# Servo2015_Logic_V1_2.net
KiCad netlist of a schematic drawn in EAGLE
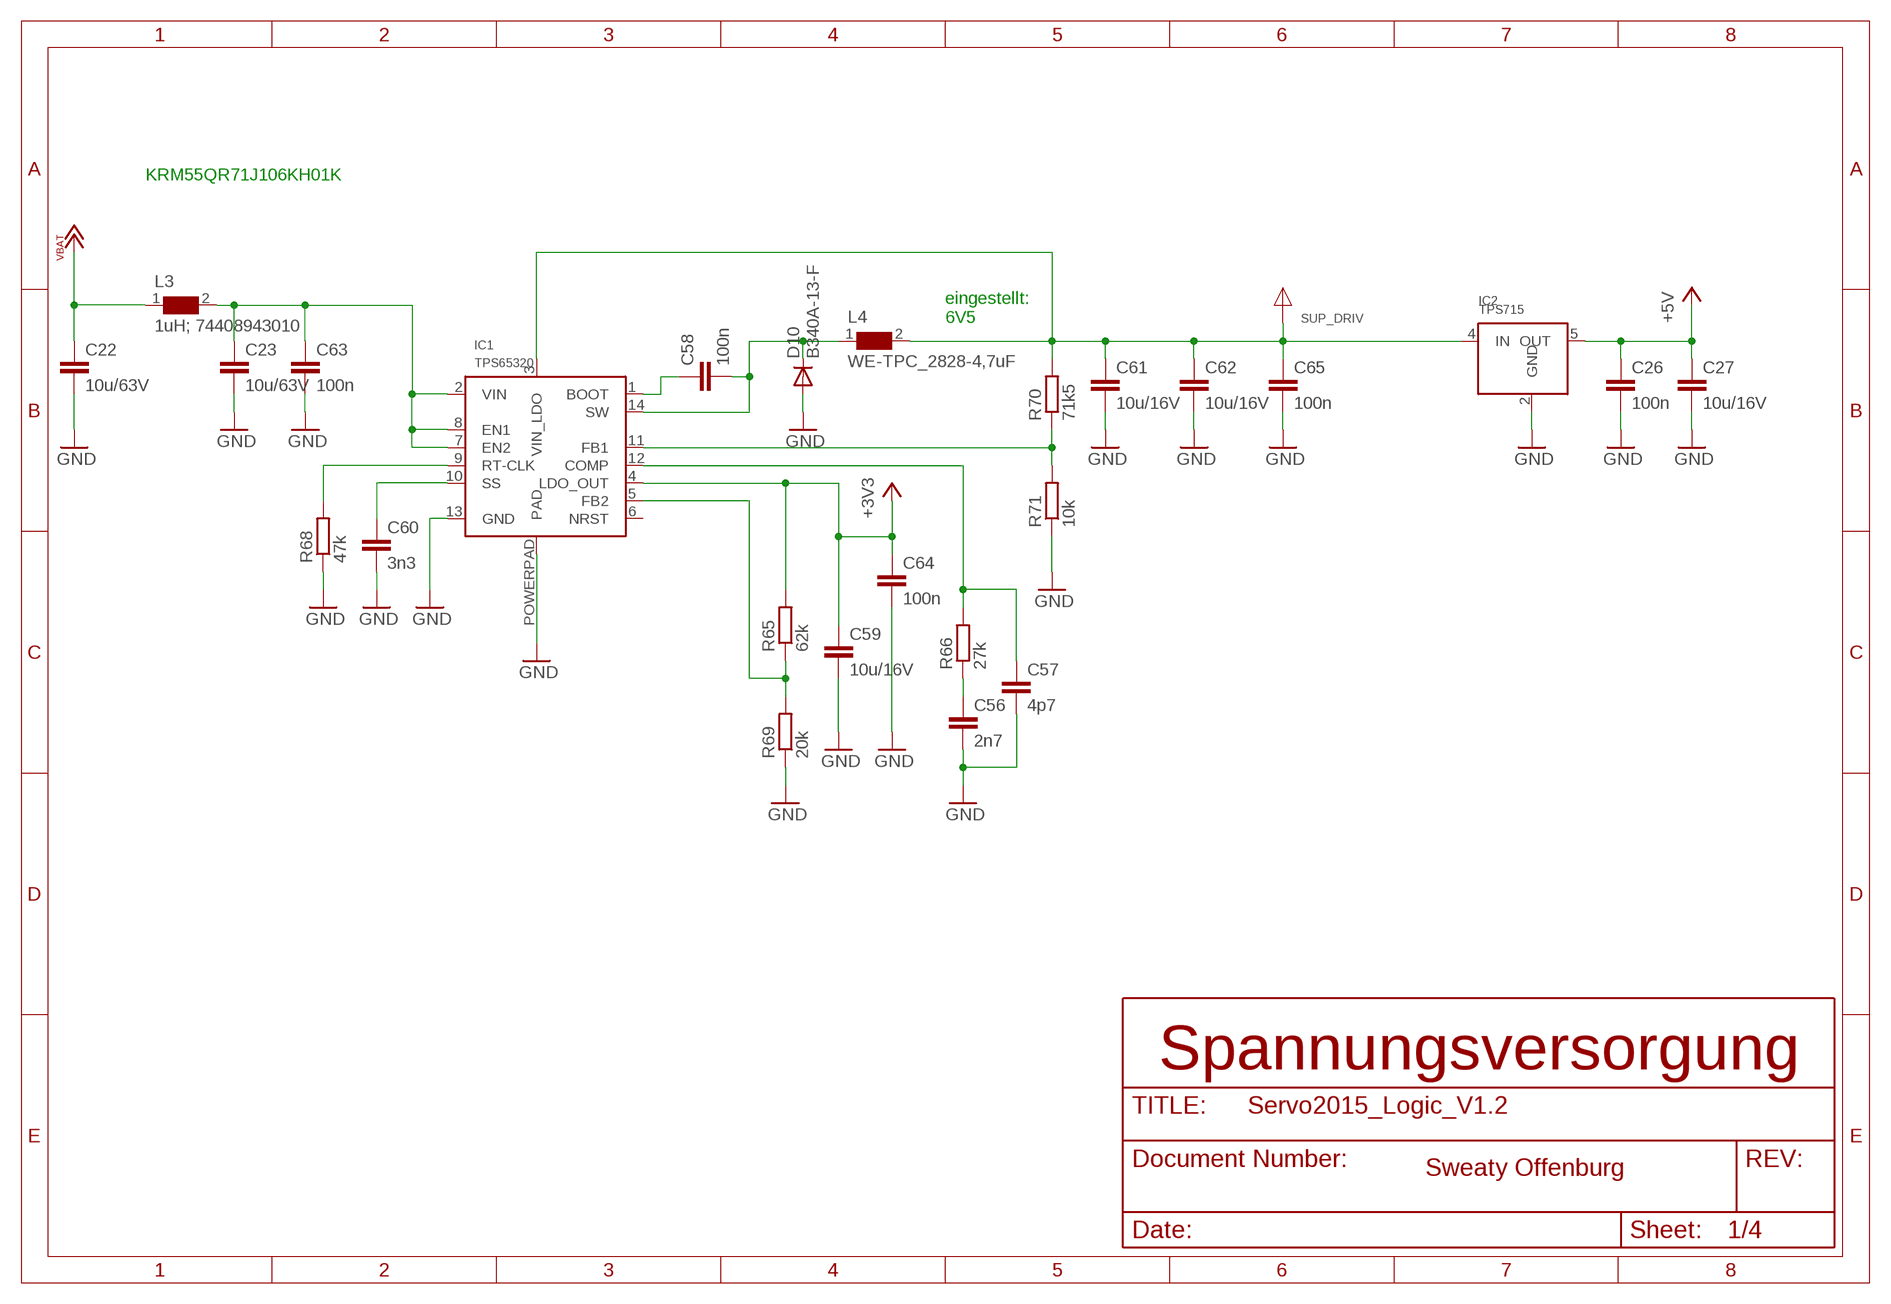
[diagram p0: schematic, sheet 1]
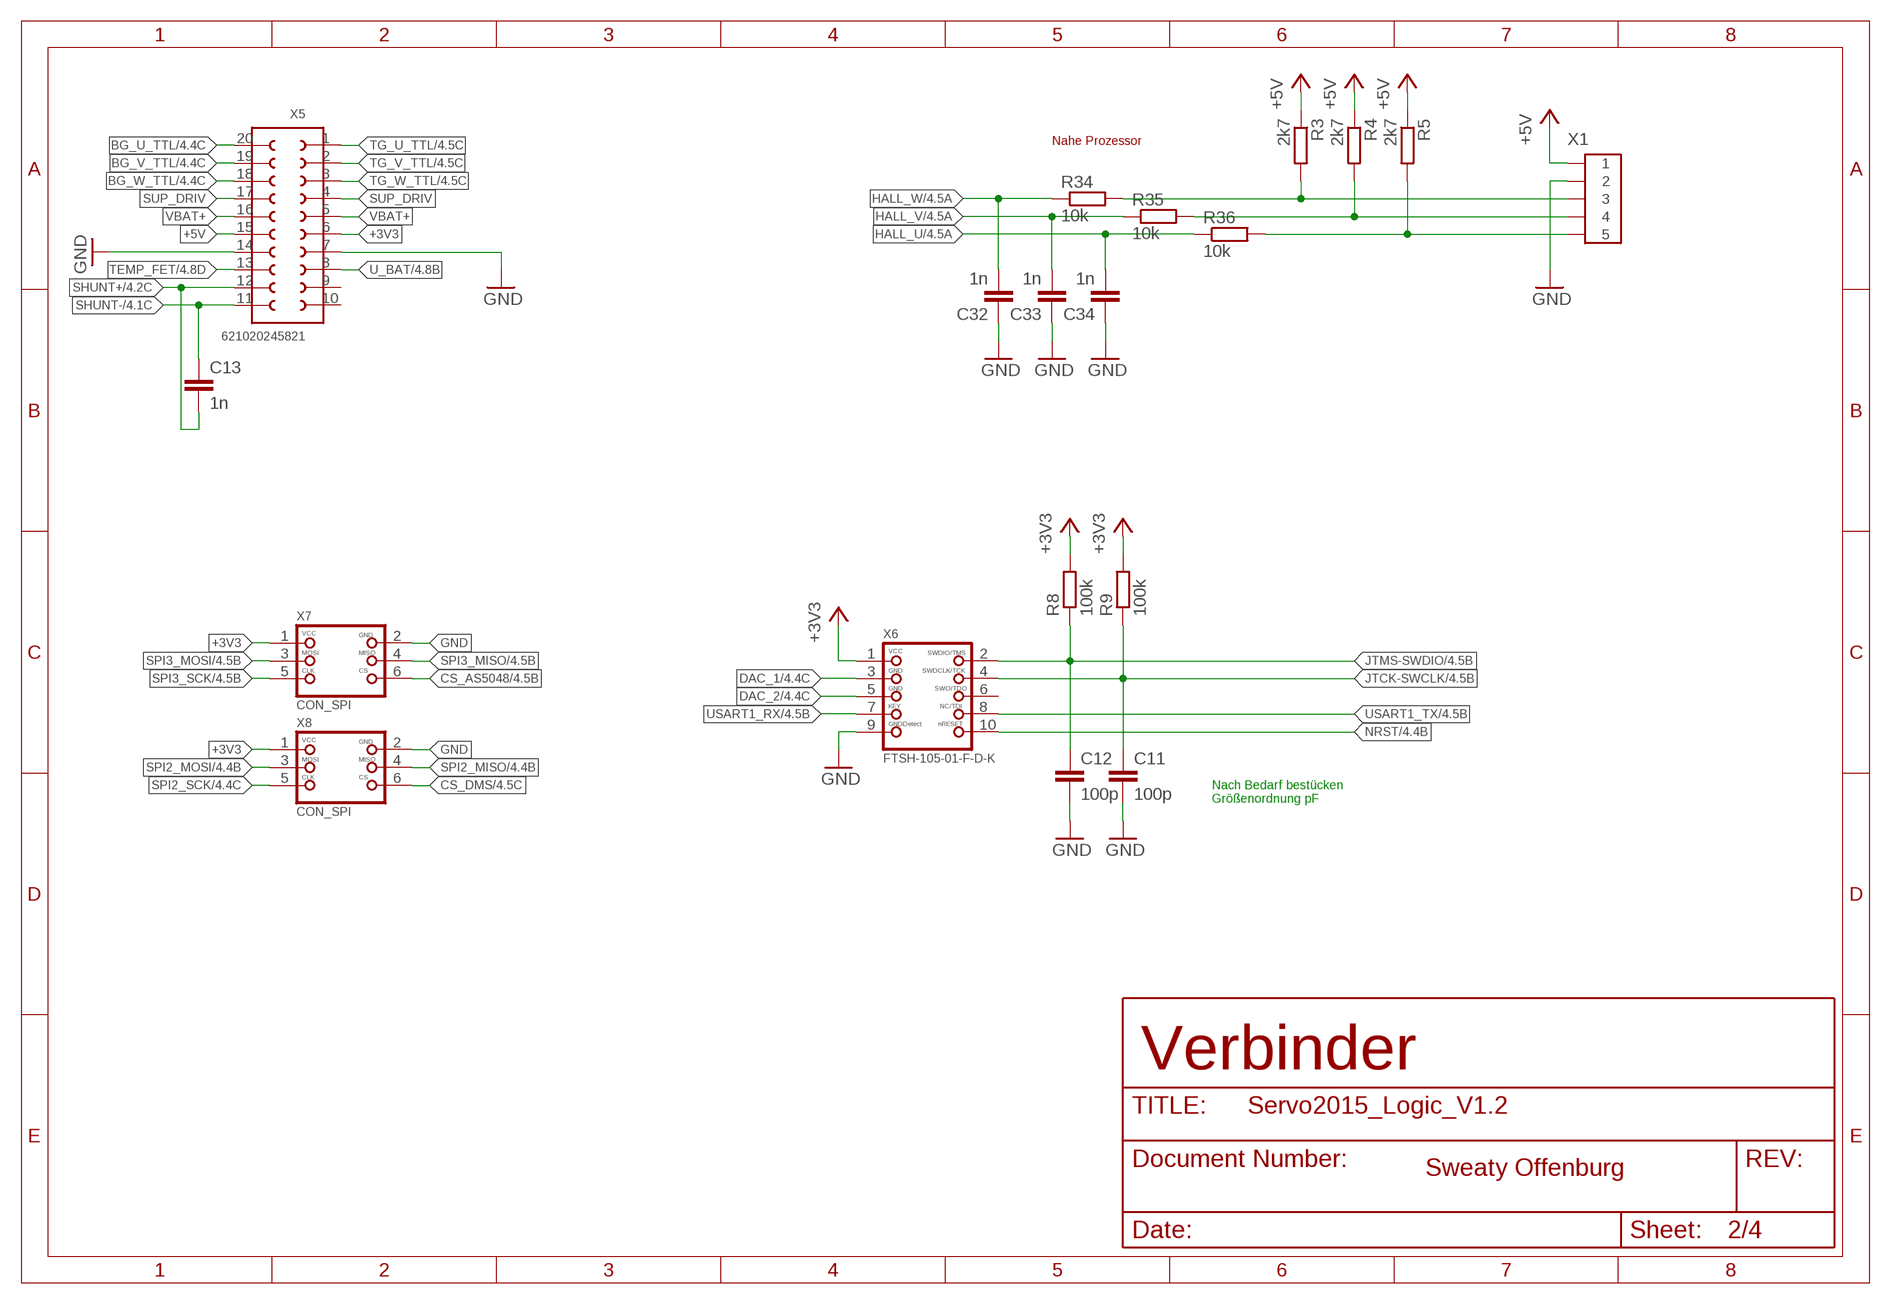
[diagram p1: schematic, sheet 2]
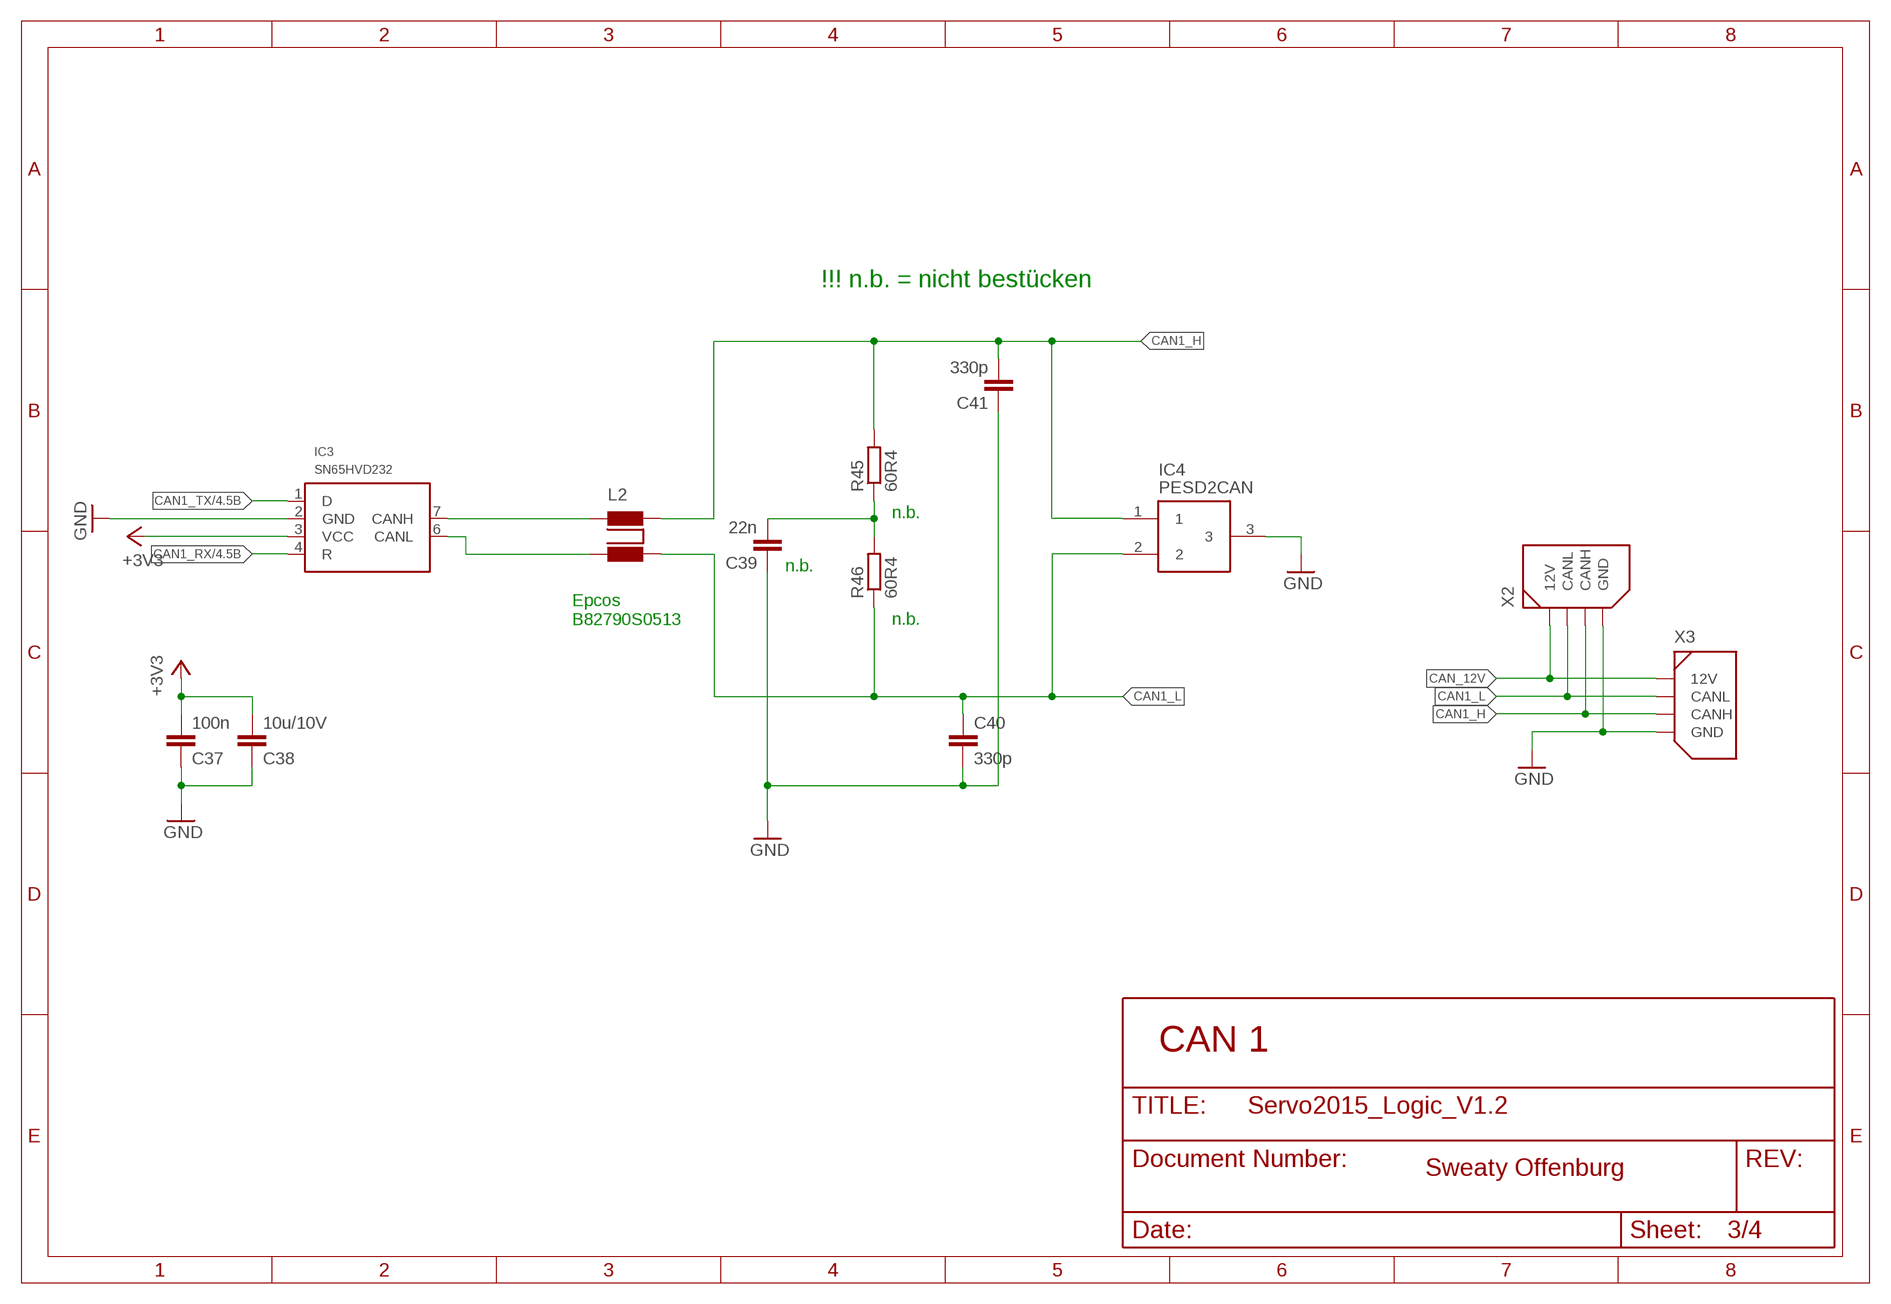
[diagram p2: schematic, sheet 3]
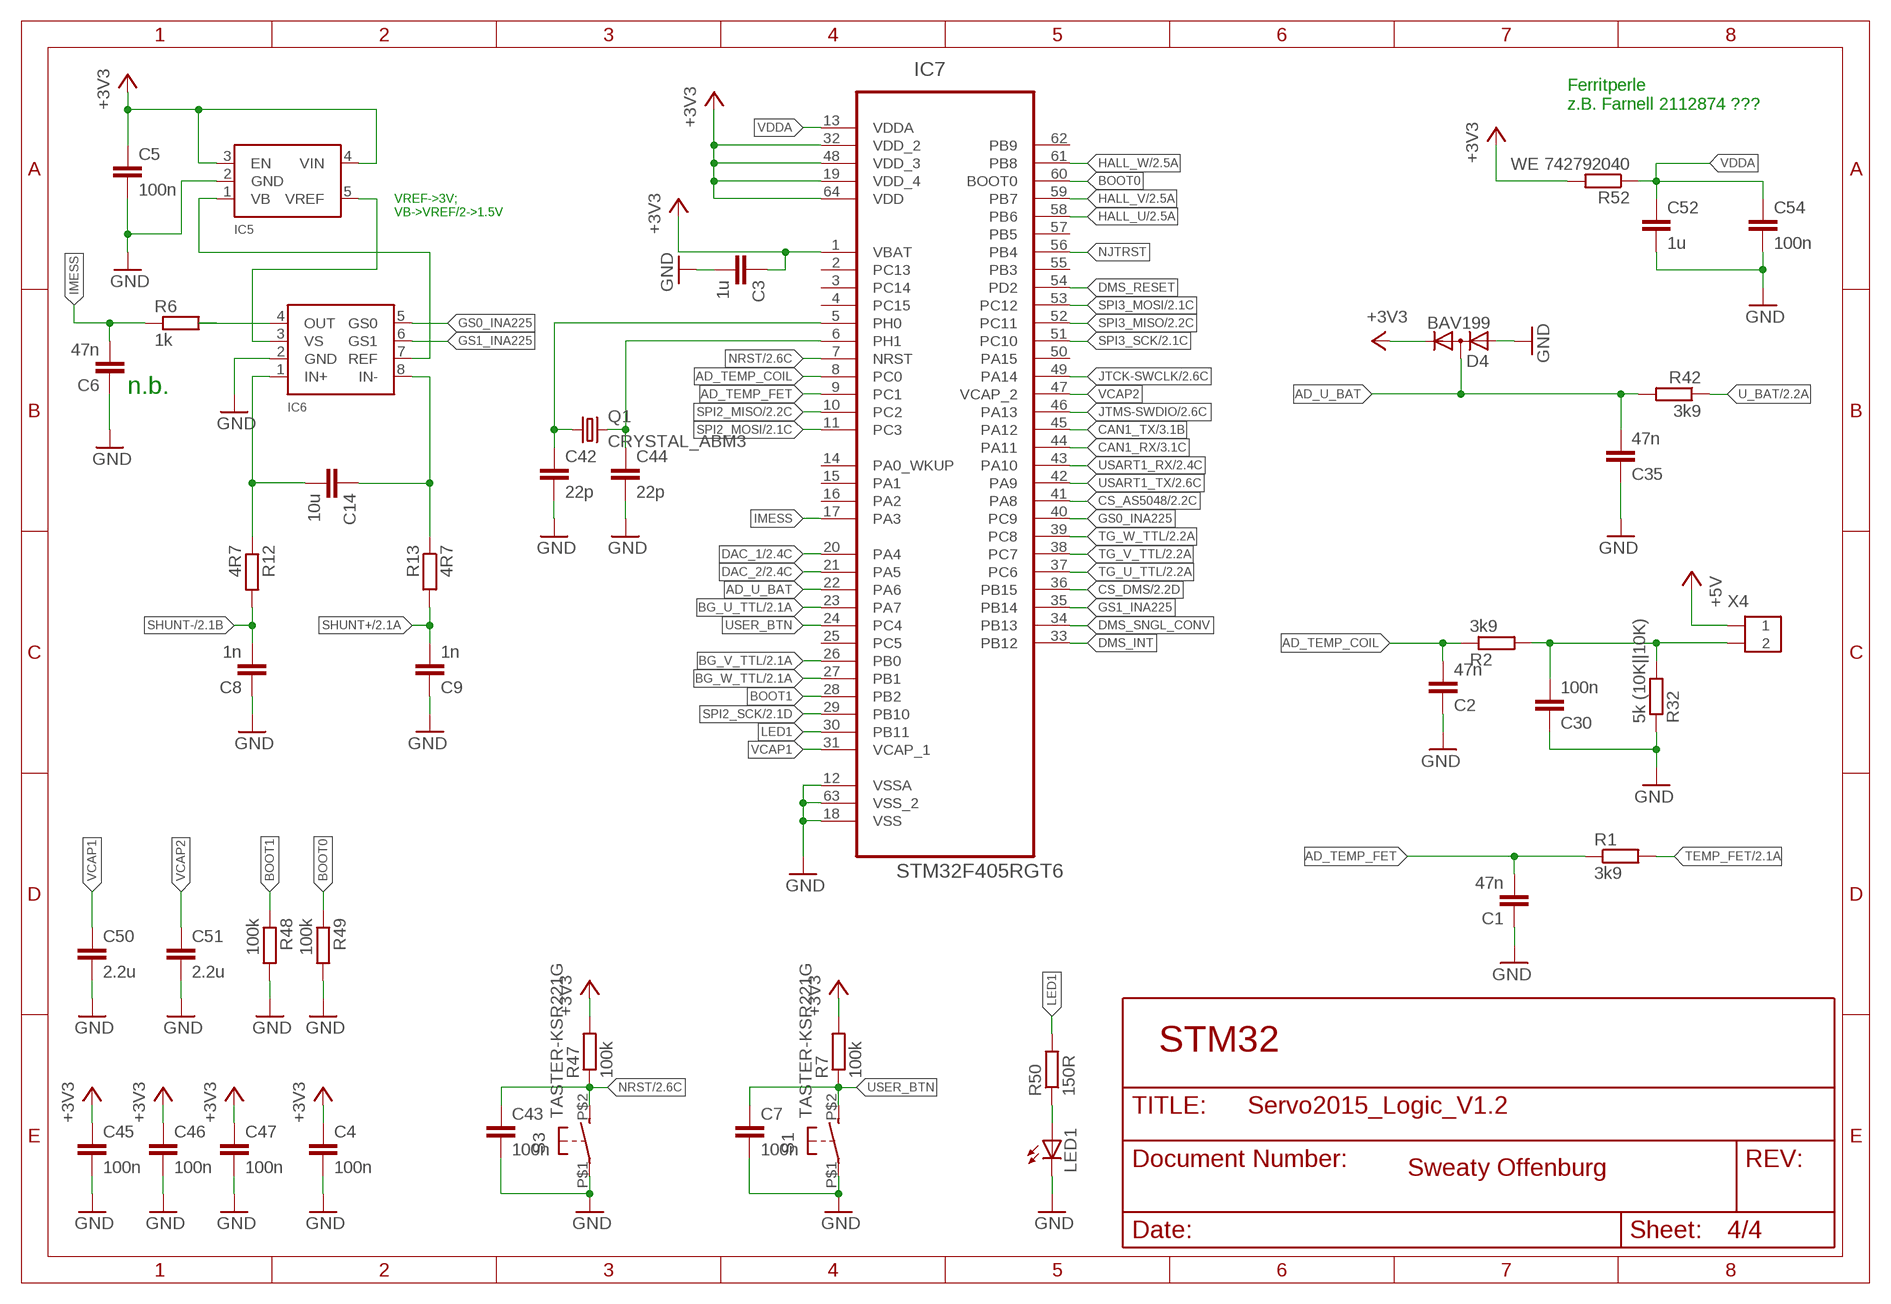
[diagram p3: schematic, sheet 4]

(export (version "E")
  (design (tool "Eeschema 10.0.6"))
  (components
    (comp (ref "C1")
      (value "47n")
      (footprint "eagle-import:C0603")
      (libsource (lib "eagle-import") (part "C-EUC0603"))
    )
    (comp (ref "C2")
      (value "47n")
      (footprint "eagle-import:C0603")
      (libsource (lib "eagle-import") (part "C-EUC0603"))
    )
    (comp (ref "C3")
      (value "1u")
      (footprint "eagle-import:C0603")
      (libsource (lib "eagle-import") (part "C-EUC0603"))
    )
    (comp (ref "C4")
      (value "100n")
      (footprint "eagle-import:C0603")
      (libsource (lib "eagle-import") (part "C-EUC0603"))
    )
    (comp (ref "C5")
      (value "100n")
      (footprint "eagle-import:C0603")
      (libsource (lib "eagle-import") (part "C-EUC0603"))
    )
    (comp (ref "C6")
      (value "47n")
      (footprint "eagle-import:C0603")
      (libsource (lib "eagle-import") (part "C-EUC0603"))
    )
    (comp (ref "C7")
      (value "100n")
      (footprint "eagle-import:C0603")
      (libsource (lib "eagle-import") (part "C-EUC0603"))
    )
    (comp (ref "C8")
      (value "1n")
      (footprint "eagle-import:C0603")
      (libsource (lib "eagle-import") (part "C-EUC0603"))
    )
    (comp (ref "C9")
      (value "1n")
      (footprint "eagle-import:C0603")
      (libsource (lib "eagle-import") (part "C-EUC0603"))
    )
    (comp (ref "C14")
      (value "10u")
      (footprint "eagle-import:C0603")
      (libsource (lib "eagle-import") (part "C-EUC0603"))
    )
    (comp (ref "C30")
      (value "100n")
      (footprint "eagle-import:C0603")
      (libsource (lib "eagle-import") (part "C-EUC0603"))
    )
    (comp (ref "C35")
      (value "47n")
      (footprint "eagle-import:C0603")
      (libsource (lib "eagle-import") (part "C-EUC0603"))
    )
    (comp (ref "C42")
      (value "22p")
      (footprint "eagle-import:C0603")
      (libsource (lib "eagle-import") (part "C-EUC0603"))
    )
    (comp (ref "C43")
      (value "100n")
      (footprint "eagle-import:C0603")
      (libsource (lib "eagle-import") (part "C-EUC0603"))
    )
    (comp (ref "C44")
      (value "22p")
      (footprint "eagle-import:C0603")
      (libsource (lib "eagle-import") (part "C-EUC0603"))
    )
    (comp (ref "C45")
      (value "100n")
      (footprint "eagle-import:C0603")
      (libsource (lib "eagle-import") (part "C-EUC0603"))
    )
    (comp (ref "C46")
      (value "100n")
      (footprint "eagle-import:C0603")
      (libsource (lib "eagle-import") (part "C-EUC0603"))
    )
    (comp (ref "C47")
      (value "100n")
      (footprint "eagle-import:C0603")
      (libsource (lib "eagle-import") (part "C-EUC0603"))
    )
    (comp (ref "C50")
      (value "2.2u")
      (footprint "eagle-import:C0603")
      (libsource (lib "eagle-import") (part "C-EUC0603"))
    )
    (comp (ref "C51")
      (value "2.2u")
      (footprint "eagle-import:C0603")
      (libsource (lib "eagle-import") (part "C-EUC0603"))
    )
    (comp (ref "C52")
      (value "1u")
      (footprint "eagle-import:C0603")
      (libsource (lib "eagle-import") (part "C-EUC0603"))
    )
    (comp (ref "C54")
      (value "100n")
      (footprint "eagle-import:C0603")
      (libsource (lib "eagle-import") (part "C-EUC0603"))
    )
    (comp (ref "D4")
      (value "BAV199")
      (footprint "eagle-import:SOT23")
      (libsource (lib "eagle-import") (part "BAV199"))
    )
    (comp (ref "IC5")
      (value "REF2030")
      (footprint "eagle-import:R-PDSO-G5")
      (libsource (lib "eagle-import") (part "REF2030"))
    )
    (comp (ref "IC6")
      (value "INA225")
      (footprint "eagle-import:S-PDSO-G8")
      (libsource (lib "eagle-import") (part "INA225"))
    )
    (comp (ref "IC7")
      (value "STM32F405RGT6")
      (footprint "eagle-import:QFP50P1200X1200X160-64N")
      (libsource (lib "eagle-import") (part "STM32F405RGT6"))
    )
    (comp (ref "LED1")
      (value "LEDCHIPLED_0805")
      (footprint "eagle-import:CHIPLED_0805")
      (libsource (lib "eagle-import") (part "LEDCHIPLED_0805"))
    )
    (comp (ref "Q1")
      (value "CRYSTAL_ABM3")
      (footprint "eagle-import:CRYSTAL-5X3.2")
      (libsource (lib "eagle-import") (part "CRYSTAL_ABM3"))
    )
    (comp (ref "R1")
      (value "3k9")
      (footprint "eagle-import:R0603")
      (libsource (lib "eagle-import") (part "R-EU_R0603"))
    )
    (comp (ref "R2")
      (value "3k9")
      (footprint "eagle-import:R0603")
      (libsource (lib "eagle-import") (part "R-EU_R0603"))
    )
    (comp (ref "R6")
      (value "1k")
      (footprint "eagle-import:R0603")
      (libsource (lib "eagle-import") (part "R-EU_R0603"))
    )
    (comp (ref "R7")
      (value "100k")
      (footprint "eagle-import:R0603")
      (libsource (lib "eagle-import") (part "R-EU_R0603"))
    )
    (comp (ref "R12")
      (value "4R7")
      (footprint "eagle-import:R0603")
      (libsource (lib "eagle-import") (part "R-EU_R0603"))
    )
    (comp (ref "R13")
      (value "4R7")
      (footprint "eagle-import:R0603")
      (libsource (lib "eagle-import") (part "R-EU_R0603"))
    )
    (comp (ref "R32")
      (value "5k (10K||10K)")
      (footprint "eagle-import:R0603")
      (libsource (lib "eagle-import") (part "R-EU_R0603"))
    )
    (comp (ref "R42")
      (value "3k9")
      (footprint "eagle-import:R0603")
      (libsource (lib "eagle-import") (part "R-EU_R0603"))
    )
    (comp (ref "R47")
      (value "100k")
      (footprint "eagle-import:R0603")
      (libsource (lib "eagle-import") (part "R-EU_R0603"))
    )
    (comp (ref "R48")
      (value "100k")
      (footprint "eagle-import:R0603")
      (libsource (lib "eagle-import") (part "R-EU_R0603"))
    )
    (comp (ref "R49")
      (value "100k")
      (footprint "eagle-import:R0603")
      (libsource (lib "eagle-import") (part "R-EU_R0603"))
    )
    (comp (ref "R50")
      (value "150R")
      (footprint "eagle-import:R0603")
      (libsource (lib "eagle-import") (part "R-EU_R0603"))
    )
    (comp (ref "R52")
      (value "WE 742792040")
      (footprint "eagle-import:R0805")
      (libsource (lib "eagle-import") (part "R-EU_R0805"))
    )
    (comp (ref "S1")
      (value "TASTER-KSR221G")
      (footprint "eagle-import:KSR-TASTER")
      (libsource (lib "eagle-import") (part "TASTER-KSR221G"))
    )
    (comp (ref "S3")
      (value "TASTER-KSR221G")
      (footprint "eagle-import:KSR-TASTER")
      (libsource (lib "eagle-import") (part "TASTER-KSR221G"))
    )
    (comp (ref "X4")
      (value "KRAFTSENSOR-2POL")
      (footprint "eagle-import:MOLEX-SPOX-2POL")
      (libsource (lib "eagle-import") (part "KRAFTSENSOR-2POL"))
    )
    (comp (ref "C37")
      (value "100n")
      (footprint "eagle-import:C0603")
      (libsource (lib "eagle-import") (part "C-EUC0603"))
    )
    (comp (ref "C38")
      (value "10u/10V")
      (footprint "eagle-import:C0603")
      (libsource (lib "eagle-import") (part "C-EUC0603"))
    )
    (comp (ref "C39")
      (value "22n")
      (footprint "eagle-import:C0603")
      (libsource (lib "eagle-import") (part "C-EUC0603"))
    )
    (comp (ref "C40")
      (value "330p")
      (footprint "eagle-import:C0603")
      (libsource (lib "eagle-import") (part "C-EUC0603"))
    )
    (comp (ref "C41")
      (value "330p")
      (footprint "eagle-import:C0603")
      (libsource (lib "eagle-import") (part "C-EUC0603"))
    )
    (comp (ref "IC3")
      (value "SN65HVD232")
      (footprint "eagle-import:SO-8")
      (libsource (lib "eagle-import") (part "SN65HVD232"))
    )
    (comp (ref "IC4")
      (value "PESD2CAN")
      (footprint "eagle-import:SOT-23(TO263AB)")
      (libsource (lib "eagle-import") (part "PESD1CAN"))
    )
    (comp (ref "L2")
      (value "B82790S0513")
      (footprint "eagle-import:B82790C0_S0")
      (libsource (lib "eagle-import") (part "B82790S0513"))
    )
    (comp (ref "R45")
      (value "60R4")
      (footprint "eagle-import:R0805")
      (libsource (lib "eagle-import") (part "R-EU_R0805"))
    )
    (comp (ref "R46")
      (value "60R4")
      (footprint "eagle-import:R0805")
      (libsource (lib "eagle-import") (part "R-EU_R0805"))
    )
    (comp (ref "X2")
      (value "CAN-4POL")
      (footprint "eagle-import:MOLEX-SPOX-4PO")
      (libsource (lib "eagle-import") (part "CAN-4POL"))
    )
    (comp (ref "X3")
      (value "CAN-4POL")
      (footprint "eagle-import:MOLEX-SPOX-4PO")
      (libsource (lib "eagle-import") (part "CAN-4POL"))
    )
    (comp (ref "C22")
      (value "10u/63V")
      (footprint "eagle-import:C2220K")
      (libsource (lib "eagle-import") (part "C-EUC2220K"))
    )
    (comp (ref "C23")
      (value "10u/63V")
      (footprint "eagle-import:C2220K")
      (libsource (lib "eagle-import") (part "C-EUC2220K"))
    )
    (comp (ref "C26")
      (value "100n")
      (footprint "eagle-import:C0603")
      (libsource (lib "eagle-import") (part "C-EUC0603"))
    )
    (comp (ref "C27")
      (value "10u/16V")
      (footprint "eagle-import:C0805")
      (libsource (lib "eagle-import") (part "C-EUC0805"))
    )
    (comp (ref "C56")
      (value "2n7")
      (footprint "eagle-import:C0603")
      (libsource (lib "eagle-import") (part "C-EUC0603"))
    )
    (comp (ref "C57")
      (value "4p7")
      (footprint "eagle-import:C0603")
      (libsource (lib "eagle-import") (part "C-EUC0603"))
    )
    (comp (ref "C58")
      (value "100n")
      (footprint "eagle-import:C0603")
      (libsource (lib "eagle-import") (part "C-EUC0603"))
    )
    (comp (ref "C59")
      (value "10u/16V")
      (footprint "eagle-import:C0805")
      (libsource (lib "eagle-import") (part "C-EUC0805"))
    )
    (comp (ref "C60")
      (value "3n3")
      (footprint "eagle-import:C0603")
      (libsource (lib "eagle-import") (part "C-EUC0603"))
    )
    (comp (ref "C61")
      (value "10u/16V")
      (footprint "eagle-import:C0805")
      (libsource (lib "eagle-import") (part "C-EUC0805"))
    )
    (comp (ref "C62")
      (value "10u/16V")
      (footprint "eagle-import:C0805")
      (libsource (lib "eagle-import") (part "C-EUC0805"))
    )
    (comp (ref "C63")
      (value "100n")
      (footprint "eagle-import:C0603")
      (libsource (lib "eagle-import") (part "C-EUC0603"))
    )
    (comp (ref "C64")
      (value "100n")
      (footprint "eagle-import:C0603")
      (libsource (lib "eagle-import") (part "C-EUC0603"))
    )
    (comp (ref "C65")
      (value "100n")
      (footprint "eagle-import:C0603")
      (libsource (lib "eagle-import") (part "C-EUC0603"))
    )
    (comp (ref "D10")
      (value "B340A-13-F")
      (footprint "eagle-import:SMA")
      (libsource (lib "eagle-import") (part "B340A-13-F"))
    )
    (comp (ref "IC1")
      (value "TPS65320")
      (footprint "eagle-import:R.PDSO.G14_PWP")
      (libsource (lib "eagle-import") (part "TPS65320"))
    )
    (comp (ref "IC2")
      (value "TPS715")
      (footprint "eagle-import:SC-70_DCK_R_PDSO_G5")
      (libsource (lib "eagle-import") (part "TPS715"))
    )
    (comp (ref "L3")
      (value "1uH; 74408943010")
      (footprint "eagle-import:WE-SPC_48XX")
      (libsource (lib "eagle-import") (part "WE-SPC_48XX_4838/4828/4818"))
    )
    (comp (ref "L4")
      (value "WE-TPC_2828-4,7uF")
      (footprint "eagle-import:WE-TPC_2828")
      (libsource (lib "eagle-import") (part "WE-TPC_2828"))
    )
    (comp (ref "R65")
      (value "62k")
      (footprint "eagle-import:R0603")
      (libsource (lib "eagle-import") (part "R-EU_R0603"))
    )
    (comp (ref "R66")
      (value "27k")
      (footprint "eagle-import:R0603")
      (libsource (lib "eagle-import") (part "R-EU_R0603"))
    )
    (comp (ref "R68")
      (value "47k")
      (footprint "eagle-import:R0603")
      (libsource (lib "eagle-import") (part "R-EU_R0603"))
    )
    (comp (ref "R69")
      (value "20k")
      (footprint "eagle-import:R0603")
      (libsource (lib "eagle-import") (part "R-EU_R0603"))
    )
    (comp (ref "R70")
      (value "71k5")
      (footprint "eagle-import:R0603")
      (libsource (lib "eagle-import") (part "R-EU_R0603"))
    )
    (comp (ref "R71")
      (value "10k")
      (footprint "eagle-import:R0603")
      (libsource (lib "eagle-import") (part "R-EU_R0603"))
    )
    (comp (ref "C11")
      (value "100p")
      (footprint "eagle-import:C0603")
      (libsource (lib "eagle-import") (part "C-EUC0603"))
    )
    (comp (ref "C12")
      (value "100p")
      (footprint "eagle-import:C0603")
      (libsource (lib "eagle-import") (part "C-EUC0603"))
    )
    (comp (ref "C13")
      (value "1n")
      (footprint "eagle-import:C0603")
      (libsource (lib "eagle-import") (part "C-EUC0603"))
    )
    (comp (ref "C32")
      (value "1n")
      (footprint "eagle-import:C0603")
      (libsource (lib "eagle-import") (part "C-EUC0603"))
    )
    (comp (ref "C33")
      (value "1n")
      (footprint "eagle-import:C0603")
      (libsource (lib "eagle-import") (part "C-EUC0603"))
    )
    (comp (ref "C34")
      (value "1n")
      (footprint "eagle-import:C0603")
      (libsource (lib "eagle-import") (part "C-EUC0603"))
    )
    (comp (ref "R3")
      (value "2k7")
      (footprint "eagle-import:R0603")
      (libsource (lib "eagle-import") (part "R-EU_R0603"))
    )
    (comp (ref "R4")
      (value "2k7")
      (footprint "eagle-import:R0603")
      (libsource (lib "eagle-import") (part "R-EU_R0603"))
    )
    (comp (ref "R5")
      (value "2k7")
      (footprint "eagle-import:R0603")
      (libsource (lib "eagle-import") (part "R-EU_R0603"))
    )
    (comp (ref "R8")
      (value "100k")
      (footprint "eagle-import:R0603")
      (libsource (lib "eagle-import") (part "R-EU_R0603"))
    )
    (comp (ref "R9")
      (value "100k")
      (footprint "eagle-import:R0603")
      (libsource (lib "eagle-import") (part "R-EU_R0603"))
    )
    (comp (ref "R34")
      (value "10k")
      (footprint "eagle-import:R0603")
      (libsource (lib "eagle-import") (part "R-EU_R0603"))
    )
    (comp (ref "R35")
      (value "10k")
      (footprint "eagle-import:R0603")
      (libsource (lib "eagle-import") (part "R-EU_R0603"))
    )
    (comp (ref "R36")
      (value "10k")
      (footprint "eagle-import:R0603")
      (libsource (lib "eagle-import") (part "R-EU_R0603"))
    )
    (comp (ref "X1")
      (value "HALL-5POL-SERVOBOARD")
      (footprint "eagle-import:MOLEX-SPOX-5POL-VERT")
      (libsource (lib "eagle-import") (part "HALL-5POL-SERVOBOARD"))
    )
    (comp (ref "X5")
      (value "621020245821")
      (footprint "eagle-import:621020245821")
      (libsource (lib "eagle-import") (part "621020245821"))
    )
    (comp (ref "X6")
      (value "FTSH-105-01-F-D-K")
      (footprint "eagle-import:2X05_1.27MM_SMT")
      (libsource (lib "eagle-import") (part "JTAG-CORTEXM3"))
    )
    (comp (ref "X7")
      (value "CON_SPI")
      (footprint "eagle-import:2X03_1.27MM_SMT")
      (libsource (lib "eagle-import") (part "CON_SPI"))
    )
    (comp (ref "X8")
      (value "CON_SPI")
      (footprint "eagle-import:2X03_1.27MM_SMT")
      (libsource (lib "eagle-import") (part "CON_SPI"))
    )
  )
  (nets
    (net (code "1") (name "+3V3") (class "Default")
      (node (ref "C3") (pin "1") (pinfunction "1_1") (pintype "passive"))
      (node (ref "C37") (pin "2") (pinfunction "2_2") (pintype "passive"))
      (node (ref "C38") (pin "2") (pinfunction "2_2") (pintype "passive"))
      (node (ref "C4") (pin "1") (pinfunction "1_1") (pintype "passive"))
      (node (ref "C45") (pin "1") (pinfunction "1_1") (pintype "passive"))
      (node (ref "C46") (pin "1") (pinfunction "1_1") (pintype "passive"))
      (node (ref "C47") (pin "1") (pinfunction "1_1") (pintype "passive"))
      (node (ref "C5") (pin "1") (pinfunction "1_1") (pintype "passive"))
      (node (ref "C59") (pin "1") (pinfunction "1_1") (pintype "passive"))
      (node (ref "C64") (pin "1") (pinfunction "1_1") (pintype "passive"))
      (node (ref "D4") (pin "2") (pinfunction "C_2") (pintype "passive"))
      (node (ref "IC1") (pin "4") (pinfunction "LDO_OUT_4") (pintype "bidirectional"))
      (node (ref "IC3") (pin "3") (pinfunction "VCC_3") (pintype "bidirectional"))
      (node (ref "IC5") (pin "3") (pinfunction "EN_3") (pintype "bidirectional"))
      (node (ref "IC5") (pin "4") (pinfunction "VIN_4") (pintype "bidirectional"))
      (node (ref "IC7") (pin "1") (pinfunction "VBAT_1") (pintype "passive"))
      (node (ref "IC7") (pin "19") (pinfunction "VDD_4_19") (pintype "power_in"))
      (node (ref "IC7") (pin "32") (pinfunction "VDD_2_32") (pintype "power_in"))
      (node (ref "IC7") (pin "48") (pinfunction "VDD_3_48") (pintype "power_in"))
      (node (ref "IC7") (pin "64") (pinfunction "VDD_64") (pintype "power_in"))
      (node (ref "R47") (pin "2") (pinfunction "2_2") (pintype "passive"))
      (node (ref "R52") (pin "2") (pinfunction "2_2") (pintype "passive"))
      (node (ref "R65") (pin "2") (pinfunction "2_2") (pintype "passive"))
      (node (ref "R7") (pin "2") (pinfunction "2_2") (pintype "passive"))
      (node (ref "R8") (pin "2") (pinfunction "2_2") (pintype "passive"))
      (node (ref "R9") (pin "2") (pinfunction "2_2") (pintype "passive"))
      (node (ref "X5") (pin "6") (pinfunction "6_6") (pintype "passive"))
      (node (ref "X6") (pin "1") (pinfunction "1_1") (pintype "passive"))
      (node (ref "X7") (pin "1") (pinfunction "1_1") (pintype "passive"))
      (node (ref "X8") (pin "1") (pinfunction "1_1") (pintype "passive"))
    )
    (net (code "2") (name "+5V") (class "Default")
      (node (ref "C26") (pin "1") (pinfunction "1_1") (pintype "passive"))
      (node (ref "C27") (pin "1") (pinfunction "1_1") (pintype "passive"))
      (node (ref "IC2") (pin "5") (pinfunction "OUT_5") (pintype "bidirectional"))
      (node (ref "R3") (pin "1") (pinfunction "1_1") (pintype "passive"))
      (node (ref "R4") (pin "1") (pinfunction "1_1") (pintype "passive"))
      (node (ref "R5") (pin "1") (pinfunction "1_1") (pintype "passive"))
      (node (ref "X1") (pin "1") (pinfunction "1_1") (pintype "bidirectional"))
      (node (ref "X4") (pin "P$1") (pinfunction "1_P$1") (pintype "bidirectional"))
      (node (ref "X5") (pin "15") (pinfunction "15_15") (pintype "passive"))
    )
    (net (code "3") (name "AD_TEMP_COIL") (class "Default")
      (node (ref "C2") (pin "2") (pinfunction "2_2") (pintype "passive"))
      (node (ref "IC7") (pin "8") (pinfunction "PC0_8") (pintype "bidirectional"))
      (node (ref "R2") (pin "1") (pinfunction "1_1") (pintype "passive"))
    )
    (net (code "4") (name "AD_TEMP_FET") (class "Default")
      (node (ref "C1") (pin "2") (pinfunction "2_2") (pintype "passive"))
      (node (ref "IC7") (pin "9") (pinfunction "PC1_9") (pintype "bidirectional"))
      (node (ref "R1") (pin "1") (pinfunction "1_1") (pintype "passive"))
    )
    (net (code "5") (name "AD_U_BAT") (class "Default")
      (node (ref "C35") (pin "2") (pinfunction "2_2") (pintype "passive"))
      (node (ref "D4") (pin "3") (pinfunction "AC_3") (pintype "passive"))
      (node (ref "IC7") (pin "22") (pinfunction "PA6_22") (pintype "bidirectional"))
      (node (ref "R42") (pin "2") (pinfunction "2_2") (pintype "passive"))
    )
    (net (code "6") (name "BG_U_TTL") (class "Default")
      (node (ref "IC7") (pin "23") (pinfunction "PA7_23") (pintype "bidirectional"))
      (node (ref "X5") (pin "20") (pinfunction "20_20") (pintype "passive"))
    )
    (net (code "7") (name "BG_V_TTL") (class "Default")
      (node (ref "IC7") (pin "26") (pinfunction "PB0_26") (pintype "bidirectional"))
      (node (ref "X5") (pin "19") (pinfunction "19_19") (pintype "passive"))
    )
    (net (code "8") (name "BG_W_TTL") (class "Default")
      (node (ref "IC7") (pin "27") (pinfunction "PB1_27") (pintype "bidirectional"))
      (node (ref "X5") (pin "18") (pinfunction "18_18") (pintype "passive"))
    )
    (net (code "9") (name "BOOT0") (class "Default")
      (node (ref "IC7") (pin "60") (pinfunction "BOOT0_60") (pintype "passive"))
      (node (ref "R49") (pin "1") (pinfunction "1_1") (pintype "passive"))
    )
    (net (code "10") (name "BOOT1") (class "Default")
      (node (ref "IC7") (pin "28") (pinfunction "PB2_28") (pintype "bidirectional"))
      (node (ref "R48") (pin "1") (pinfunction "1_1") (pintype "passive"))
    )
    (net (code "11") (name "CAN1_H") (class "Default")
      (node (ref "C41") (pin "2") (pinfunction "2_2") (pintype "passive"))
      (node (ref "IC4") (pin "1") (pinfunction "1_1") (pintype "bidirectional"))
      (node (ref "L2") (pin "2") (pinfunction "2_2") (pintype "bidirectional"))
      (node (ref "R45") (pin "2") (pinfunction "2_2") (pintype "passive"))
      (node (ref "X2") (pin "P$3") (pinfunction "CANH_P$3") (pintype "power_in"))
      (node (ref "X3") (pin "P$3") (pinfunction "CANH_P$3") (pintype "power_in"))
    )
    (net (code "12") (name "CAN1_L") (class "Default")
      (node (ref "C40") (pin "1") (pinfunction "1_1") (pintype "passive"))
      (node (ref "IC4") (pin "2") (pinfunction "2_2") (pintype "bidirectional"))
      (node (ref "L2") (pin "3") (pinfunction "3_3") (pintype "bidirectional"))
      (node (ref "R46") (pin "1") (pinfunction "1_1") (pintype "passive"))
      (node (ref "X2") (pin "P$2") (pinfunction "CANL_P$2") (pintype "bidirectional"))
      (node (ref "X3") (pin "P$2") (pinfunction "CANL_P$2") (pintype "bidirectional"))
    )
    (net (code "13") (name "CAN1_RX") (class "Default")
      (node (ref "IC3") (pin "4") (pinfunction "R_4") (pintype "bidirectional"))
      (node (ref "IC7") (pin "44") (pinfunction "PA11_44") (pintype "bidirectional"))
    )
    (net (code "14") (name "CAN1_TX") (class "Default")
      (node (ref "IC3") (pin "1") (pinfunction "D_1") (pintype "bidirectional"))
      (node (ref "IC7") (pin "45") (pinfunction "PA12_45") (pintype "bidirectional"))
    )
    (net (code "15") (name "CAN_12V") (class "Default")
      (node (ref "X2") (pin "P$1") (pinfunction "12V_P$1") (pintype "bidirectional"))
      (node (ref "X3") (pin "P$1") (pinfunction "12V_P$1") (pintype "bidirectional"))
    )
    (net (code "16") (name "CS_AS5048") (class "Default")
      (node (ref "IC7") (pin "41") (pinfunction "PA8_41") (pintype "bidirectional"))
      (node (ref "X7") (pin "6") (pinfunction "6_6") (pintype "passive"))
    )
    (net (code "17") (name "CS_DMS") (class "Default")
      (node (ref "IC7") (pin "36") (pinfunction "PB15_36") (pintype "bidirectional"))
      (node (ref "X8") (pin "6") (pinfunction "6_6") (pintype "passive"))
    )
    (net (code "18") (name "DAC_1") (class "Default")
      (node (ref "IC7") (pin "20") (pinfunction "PA4_20") (pintype "bidirectional"))
      (node (ref "X6") (pin "3") (pinfunction "3_3") (pintype "passive"))
    )
    (net (code "19") (name "DAC_2") (class "Default")
      (node (ref "IC7") (pin "21") (pinfunction "PA5_21") (pintype "bidirectional"))
      (node (ref "X6") (pin "5") (pinfunction "5_5") (pintype "passive"))
    )
    (net (code "20") (name "DMS_INT") (class "Default")
      (node (ref "IC7") (pin "33") (pinfunction "PB12_33") (pintype "bidirectional"))
    )
    (net (code "21") (name "DMS_RESET") (class "Default")
      (node (ref "IC7") (pin "54") (pinfunction "PD2_54") (pintype "bidirectional"))
    )
    (net (code "22") (name "DMS_SNGL_CONV") (class "Default")
      (node (ref "IC7") (pin "34") (pinfunction "PB13_34") (pintype "bidirectional"))
    )
    (net (code "23") (name "GND") (class "Default")
      (node (ref "C1") (pin "1") (pinfunction "1_1") (pintype "passive"))
      (node (ref "C11") (pin "2") (pinfunction "2_2") (pintype "passive"))
      (node (ref "C12") (pin "2") (pinfunction "2_2") (pintype "passive"))
      (node (ref "C2") (pin "1") (pinfunction "1_1") (pintype "passive"))
      (node (ref "C22") (pin "2") (pinfunction "2_2") (pintype "passive"))
      (node (ref "C23") (pin "2") (pinfunction "2_2") (pintype "passive"))
      (node (ref "C26") (pin "2") (pinfunction "2_2") (pintype "passive"))
      (node (ref "C27") (pin "2") (pinfunction "2_2") (pintype "passive"))
      (node (ref "C3") (pin "2") (pinfunction "2_2") (pintype "passive"))
      (node (ref "C30") (pin "1") (pinfunction "1_1") (pintype "passive"))
      (node (ref "C32") (pin "1") (pinfunction "1_1") (pintype "passive"))
      (node (ref "C33") (pin "1") (pinfunction "1_1") (pintype "passive"))
      (node (ref "C34") (pin "1") (pinfunction "1_1") (pintype "passive"))
      (node (ref "C35") (pin "1") (pinfunction "1_1") (pintype "passive"))
      (node (ref "C37") (pin "1") (pinfunction "1_1") (pintype "passive"))
      (node (ref "C38") (pin "1") (pinfunction "1_1") (pintype "passive"))
      (node (ref "C39") (pin "1") (pinfunction "1_1") (pintype "passive"))
      (node (ref "C4") (pin "2") (pinfunction "2_2") (pintype "passive"))
      (node (ref "C40") (pin "2") (pinfunction "2_2") (pintype "passive"))
      (node (ref "C41") (pin "1") (pinfunction "1_1") (pintype "passive"))
      (node (ref "C42") (pin "2") (pinfunction "2_2") (pintype "passive"))
      (node (ref "C43") (pin "2") (pinfunction "2_2") (pintype "passive"))
      (node (ref "C44") (pin "2") (pinfunction "2_2") (pintype "passive"))
      (node (ref "C45") (pin "2") (pinfunction "2_2") (pintype "passive"))
      (node (ref "C46") (pin "2") (pinfunction "2_2") (pintype "passive"))
      (node (ref "C47") (pin "2") (pinfunction "2_2") (pintype "passive"))
      (node (ref "C5") (pin "2") (pinfunction "2_2") (pintype "passive"))
      (node (ref "C50") (pin "2") (pinfunction "2_2") (pintype "passive"))
      (node (ref "C51") (pin "2") (pinfunction "2_2") (pintype "passive"))
      (node (ref "C52") (pin "2") (pinfunction "2_2") (pintype "passive"))
      (node (ref "C54") (pin "2") (pinfunction "2_2") (pintype "passive"))
      (node (ref "C56") (pin "2") (pinfunction "2_2") (pintype "passive"))
      (node (ref "C57") (pin "2") (pinfunction "2_2") (pintype "passive"))
      (node (ref "C59") (pin "2") (pinfunction "2_2") (pintype "passive"))
      (node (ref "C6") (pin "1") (pinfunction "1_1") (pintype "passive"))
      (node (ref "C60") (pin "2") (pinfunction "2_2") (pintype "passive"))
      (node (ref "C61") (pin "2") (pinfunction "2_2") (pintype "passive"))
      (node (ref "C62") (pin "2") (pinfunction "2_2") (pintype "passive"))
      (node (ref "C63") (pin "2") (pinfunction "2_2") (pintype "passive"))
      (node (ref "C64") (pin "2") (pinfunction "2_2") (pintype "passive"))
      (node (ref "C65") (pin "2") (pinfunction "2_2") (pintype "passive"))
      (node (ref "C7") (pin "2") (pinfunction "2_2") (pintype "passive"))
      (node (ref "C8") (pin "1") (pinfunction "1_1") (pintype "passive"))
      (node (ref "C9") (pin "1") (pinfunction "1_1") (pintype "passive"))
      (node (ref "D10") (pin "A") (pinfunction "A_A") (pintype "passive"))
      (node (ref "D4") (pin "1") (pinfunction "A_1") (pintype "passive"))
      (node (ref "IC1") (pin "13") (pinfunction "GND_13") (pintype "bidirectional"))
      (node (ref "IC1") (pin "POWERPAD") (pinfunction "PAD_POWERPAD") (pintype "bidirectional"))
      (node (ref "IC2") (pin "2") (pinfunction "GND_2") (pintype "bidirectional"))
      (node (ref "IC3") (pin "2") (pinfunction "GND_2") (pintype "bidirectional"))
      (node (ref "IC4") (pin "3") (pinfunction "3_3") (pintype "bidirectional"))
      (node (ref "IC5") (pin "2") (pinfunction "GND_2") (pintype "bidirectional"))
      (node (ref "IC6") (pin "2") (pinfunction "GND_2") (pintype "bidirectional"))
      (node (ref "IC7") (pin "12") (pinfunction "VSSA_12") (pintype "power_in"))
      (node (ref "IC7") (pin "18") (pinfunction "VSS_18") (pintype "power_in"))
      (node (ref "IC7") (pin "63") (pinfunction "VSS_2_63") (pintype "power_in"))
      (node (ref "LED1") (pin "C") (pinfunction "C_C") (pintype "passive"))
      (node (ref "R32") (pin "1") (pinfunction "1_1") (pintype "passive"))
      (node (ref "R48") (pin "2") (pinfunction "2_2") (pintype "passive"))
      (node (ref "R49") (pin "2") (pinfunction "2_2") (pintype "passive"))
      (node (ref "R68") (pin "1") (pinfunction "1_1") (pintype "passive"))
      (node (ref "R69") (pin "1") (pinfunction "1_1") (pintype "passive"))
      (node (ref "R71") (pin "1") (pinfunction "1_1") (pintype "passive"))
      (node (ref "S1") (pin "P$1") (pinfunction "P_P$1") (pintype "passive"))
      (node (ref "S3") (pin "P$1") (pinfunction "P_P$1") (pintype "passive"))
      (node (ref "X1") (pin "2") (pinfunction "2_2") (pintype "bidirectional"))
      (node (ref "X2") (pin "P$4") (pinfunction "GND_P$4") (pintype "power_in"))
      (node (ref "X3") (pin "P$4") (pinfunction "GND_P$4") (pintype "power_in"))
      (node (ref "X5") (pin "14") (pinfunction "14_14") (pintype "passive"))
      (node (ref "X5") (pin "7") (pinfunction "7_7") (pintype "passive"))
      (node (ref "X6") (pin "9") (pinfunction "9_9") (pintype "passive"))
      (node (ref "X7") (pin "2") (pinfunction "2_2") (pintype "passive"))
      (node (ref "X8") (pin "2") (pinfunction "2_2") (pintype "passive"))
    )
    (net (code "24") (name "GS0_INA225") (class "Default")
      (node (ref "IC6") (pin "5") (pinfunction "GS0_5") (pintype "bidirectional"))
      (node (ref "IC7") (pin "40") (pinfunction "PC9_40") (pintype "bidirectional"))
    )
    (net (code "25") (name "GS1_INA225") (class "Default")
      (node (ref "IC6") (pin "6") (pinfunction "GS1_6") (pintype "bidirectional"))
      (node (ref "IC7") (pin "35") (pinfunction "PB14_35") (pintype "bidirectional"))
    )
    (net (code "26") (name "HALL_U") (class "Default")
      (node (ref "C34") (pin "2") (pinfunction "2_2") (pintype "passive"))
      (node (ref "IC7") (pin "58") (pinfunction "PB6_58") (pintype "bidirectional"))
      (node (ref "R36") (pin "1") (pinfunction "1_1") (pintype "passive"))
    )
    (net (code "27") (name "HALL_V") (class "Default")
      (node (ref "C33") (pin "2") (pinfunction "2_2") (pintype "passive"))
      (node (ref "IC7") (pin "59") (pinfunction "PB7_59") (pintype "bidirectional"))
      (node (ref "R35") (pin "1") (pinfunction "1_1") (pintype "passive"))
    )
    (net (code "28") (name "HALL_W") (class "Default")
      (node (ref "C32") (pin "2") (pinfunction "2_2") (pintype "passive"))
      (node (ref "IC7") (pin "61") (pinfunction "PB8_61") (pintype "bidirectional"))
      (node (ref "R34") (pin "1") (pinfunction "1_1") (pintype "passive"))
    )
    (net (code "29") (name "IMESS") (class "Default")
      (node (ref "C6") (pin "2") (pinfunction "2_2") (pintype "passive"))
      (node (ref "IC7") (pin "17") (pinfunction "PA3_17") (pintype "bidirectional"))
      (node (ref "R6") (pin "1") (pinfunction "1_1") (pintype "passive"))
    )
    (net (code "30") (name "JTCK-SWCLK") (class "Default")
      (node (ref "C11") (pin "1") (pinfunction "1_1") (pintype "passive"))
      (node (ref "IC7") (pin "49") (pinfunction "PA14_49") (pintype "bidirectional"))
      (node (ref "R9") (pin "1") (pinfunction "1_1") (pintype "passive"))
      (node (ref "X6") (pin "4") (pinfunction "4_4") (pintype "passive"))
    )
    (net (code "31") (name "JTMS-SWDIO") (class "Default")
      (node (ref "C12") (pin "1") (pinfunction "1_1") (pintype "passive"))
      (node (ref "IC7") (pin "46") (pinfunction "PA13_46") (pintype "bidirectional"))
      (node (ref "R8") (pin "1") (pinfunction "1_1") (pintype "passive"))
      (node (ref "X6") (pin "2") (pinfunction "2_2") (pintype "passive"))
    )
    (net (code "32") (name "LED1") (class "Default")
      (node (ref "IC7") (pin "30") (pinfunction "PB11_30") (pintype "bidirectional"))
      (node (ref "R50") (pin "2") (pinfunction "2_2") (pintype "passive"))
    )
    (net (code "33") (name "NJTRST") (class "Default")
      (node (ref "IC7") (pin "56") (pinfunction "PB4_56") (pintype "bidirectional"))
    )
    (net (code "34") (name "NRST") (class "Default")
      (node (ref "C43") (pin "1") (pinfunction "1_1") (pintype "passive"))
      (node (ref "IC7") (pin "7") (pinfunction "NRST_7") (pintype "passive"))
      (node (ref "R47") (pin "1") (pinfunction "1_1") (pintype "passive"))
      (node (ref "S3") (pin "P$2") (pinfunction "S_P$2") (pintype "passive"))
      (node (ref "X6") (pin "10") (pinfunction "10_10") (pintype "passive"))
    )
    (net (code "35") (name "Net-(C39-Pad2)") (class "Default")
      (node (ref "C39") (pin "2") (pinfunction "2_2") (pintype "passive"))
      (node (ref "R45") (pin "1") (pinfunction "1_1") (pintype "passive"))
      (node (ref "R46") (pin "2") (pinfunction "2_2") (pintype "passive"))
    )
    (net (code "36") (name "Net-(C56-Pad1)") (class "Default")
      (node (ref "C56") (pin "1") (pinfunction "1_1") (pintype "passive"))
      (node (ref "R66") (pin "1") (pinfunction "1_1") (pintype "passive"))
    )
    (net (code "37") (name "Net-(IC1-BOOT)") (class "Default")
      (node (ref "C58") (pin "1") (pinfunction "1_1") (pintype "passive"))
      (node (ref "IC1") (pin "1") (pinfunction "BOOT_1") (pintype "bidirectional"))
    )
    (net (code "38") (name "Net-(IC1-COMP)") (class "Default")
      (node (ref "C57") (pin "1") (pinfunction "1_1") (pintype "passive"))
      (node (ref "IC1") (pin "12") (pinfunction "COMP_12") (pintype "bidirectional"))
      (node (ref "R66") (pin "2") (pinfunction "2_2") (pintype "passive"))
    )
    (net (code "39") (name "Net-(IC1-EN1)") (class "Default")
      (node (ref "C23") (pin "1") (pinfunction "1_1") (pintype "passive"))
      (node (ref "C63") (pin "1") (pinfunction "1_1") (pintype "passive"))
      (node (ref "IC1") (pin "2") (pinfunction "VIN_2") (pintype "bidirectional"))
      (node (ref "IC1") (pin "7") (pinfunction "EN2_7") (pintype "bidirectional"))
      (node (ref "IC1") (pin "8") (pinfunction "EN1_8") (pintype "bidirectional"))
      (node (ref "L3") (pin "2") (pinfunction "2_2") (pintype "passive"))
    )
    (net (code "40") (name "Net-(IC1-FB1)") (class "Default")
      (node (ref "IC1") (pin "11") (pinfunction "FB1_11") (pintype "bidirectional"))
      (node (ref "R70") (pin "1") (pinfunction "1_1") (pintype "passive"))
      (node (ref "R71") (pin "2") (pinfunction "2_2") (pintype "passive"))
    )
    (net (code "41") (name "Net-(IC1-FB2)") (class "Default")
      (node (ref "IC1") (pin "5") (pinfunction "FB2_5") (pintype "bidirectional"))
      (node (ref "R65") (pin "1") (pinfunction "1_1") (pintype "passive"))
      (node (ref "R69") (pin "2") (pinfunction "2_2") (pintype "passive"))
    )
    (net (code "42") (name "Net-(IC1-RT-CLK)") (class "Default")
      (node (ref "IC1") (pin "9") (pinfunction "RT-CLK_9") (pintype "bidirectional"))
      (node (ref "R68") (pin "2") (pinfunction "2_2") (pintype "passive"))
    )
    (net (code "43") (name "Net-(IC1-SS)") (class "Default")
      (node (ref "C60") (pin "1") (pinfunction "1_1") (pintype "passive"))
      (node (ref "IC1") (pin "10") (pinfunction "SS_10") (pintype "bidirectional"))
    )
    (net (code "44") (name "Net-(IC1-SW)") (class "Default")
      (node (ref "C58") (pin "2") (pinfunction "2_2") (pintype "passive"))
      (node (ref "D10") (pin "C") (pinfunction "C_C") (pintype "passive"))
      (node (ref "IC1") (pin "14") (pinfunction "SW_14") (pintype "bidirectional"))
      (node (ref "L4") (pin "1") (pinfunction "1_1") (pintype "passive"))
    )
    (net (code "45") (name "Net-(IC3-CANH)") (class "Default")
      (node (ref "IC3") (pin "7") (pinfunction "CANH_7") (pintype "bidirectional"))
      (node (ref "L2") (pin "1") (pinfunction "1_1") (pintype "bidirectional"))
    )
    (net (code "46") (name "Net-(IC3-CANL)") (class "Default")
      (node (ref "IC3") (pin "6") (pinfunction "CANL_6") (pintype "bidirectional"))
      (node (ref "L2") (pin "4") (pinfunction "4_4") (pintype "bidirectional"))
    )
    (net (code "47") (name "Net-(IC5-VB)") (class "Default")
      (node (ref "IC5") (pin "1") (pinfunction "VB_1") (pintype "bidirectional"))
      (node (ref "IC6") (pin "7") (pinfunction "REF_7") (pintype "bidirectional"))
    )
    (net (code "48") (name "Net-(IC5-VREF)") (class "Default")
      (node (ref "IC5") (pin "5") (pinfunction "VREF_5") (pintype "bidirectional"))
      (node (ref "IC6") (pin "3") (pinfunction "VS_3") (pintype "bidirectional"))
    )
    (net (code "49") (name "Net-(IC6-IN+)") (class "Default")
      (node (ref "C14") (pin "2") (pinfunction "2_2") (pintype "passive"))
      (node (ref "IC6") (pin "1") (pinfunction "IN+_1") (pintype "bidirectional"))
      (node (ref "R12") (pin "1") (pinfunction "1_1") (pintype "passive"))
    )
    (net (code "50") (name "Net-(IC6-IN-)") (class "Default")
      (node (ref "C14") (pin "1") (pinfunction "1_1") (pintype "passive"))
      (node (ref "IC6") (pin "8") (pinfunction "IN-_8") (pintype "bidirectional"))
      (node (ref "R13") (pin "1") (pinfunction "1_1") (pintype "passive"))
    )
    (net (code "51") (name "Net-(IC6-OUT)") (class "Default")
      (node (ref "IC6") (pin "4") (pinfunction "OUT_4") (pintype "bidirectional"))
      (node (ref "R6") (pin "2") (pinfunction "2_2") (pintype "passive"))
    )
    (net (code "52") (name "Net-(IC7-PH0)") (class "Default")
      (node (ref "C42") (pin "1") (pinfunction "1_1") (pintype "passive"))
      (node (ref "IC7") (pin "5") (pinfunction "PH0_5") (pintype "bidirectional"))
      (node (ref "Q1") (pin "P$1") (pinfunction "1_P$1") (pintype "passive"))
    )
    (net (code "53") (name "Net-(IC7-PH1)") (class "Default")
      (node (ref "C44") (pin "1") (pinfunction "1_1") (pintype "passive"))
      (node (ref "IC7") (pin "6") (pinfunction "PH1_6") (pintype "bidirectional"))
      (node (ref "Q1") (pin "P$2") (pinfunction "2_P$2") (pintype "passive"))
    )
    (net (code "54") (name "Net-(LED1-PadA)") (class "Default")
      (node (ref "LED1") (pin "A") (pinfunction "A_A") (pintype "passive"))
      (node (ref "R50") (pin "1") (pinfunction "1_1") (pintype "passive"))
    )
    (net (code "55") (name "Net-(R3-Pad2)") (class "Default")
      (node (ref "R3") (pin "2") (pinfunction "2_2") (pintype "passive"))
      (node (ref "R34") (pin "2") (pinfunction "2_2") (pintype "passive"))
      (node (ref "X1") (pin "3") (pinfunction "3_3") (pintype "bidirectional"))
    )
    (net (code "56") (name "Net-(R35-Pad2)") (class "Default")
      (node (ref "R35") (pin "2") (pinfunction "2_2") (pintype "passive"))
      (node (ref "R4") (pin "2") (pinfunction "2_2") (pintype "passive"))
      (node (ref "X1") (pin "4") (pinfunction "4_4") (pintype "bidirectional"))
    )
    (net (code "57") (name "Net-(R36-Pad2)") (class "Default")
      (node (ref "R36") (pin "2") (pinfunction "2_2") (pintype "passive"))
      (node (ref "R5") (pin "2") (pinfunction "2_2") (pintype "passive"))
      (node (ref "X1") (pin "5") (pinfunction "5_5") (pintype "bidirectional"))
    )
    (net (code "58") (name "Net-(X4-2)") (class "Default")
      (node (ref "C30") (pin "2") (pinfunction "2_2") (pintype "passive"))
      (node (ref "R2") (pin "2") (pinfunction "2_2") (pintype "passive"))
      (node (ref "R32") (pin "2") (pinfunction "2_2") (pintype "passive"))
      (node (ref "X4") (pin "P$2") (pinfunction "2_P$2") (pintype "bidirectional"))
    )
    (net (code "59") (name "SHUNT+") (class "Default")
      (node (ref "C13") (pin "2") (pinfunction "2_2") (pintype "passive"))
      (node (ref "C9") (pin "2") (pinfunction "2_2") (pintype "passive"))
      (node (ref "R13") (pin "2") (pinfunction "2_2") (pintype "passive"))
      (node (ref "X5") (pin "12") (pinfunction "12_12") (pintype "passive"))
    )
    (net (code "60") (name "SHUNT-") (class "Default")
      (node (ref "C13") (pin "1") (pinfunction "1_1") (pintype "passive"))
      (node (ref "C8") (pin "2") (pinfunction "2_2") (pintype "passive"))
      (node (ref "R12") (pin "2") (pinfunction "2_2") (pintype "passive"))
      (node (ref "X5") (pin "11") (pinfunction "11_11") (pintype "passive"))
    )
    (net (code "61") (name "SPI2_MISO") (class "Default")
      (node (ref "IC7") (pin "10") (pinfunction "PC2_10") (pintype "bidirectional"))
      (node (ref "X8") (pin "4") (pinfunction "4_4") (pintype "passive"))
    )
    (net (code "62") (name "SPI2_MOSI") (class "Default")
      (node (ref "IC7") (pin "11") (pinfunction "PC3_11") (pintype "bidirectional"))
      (node (ref "X8") (pin "3") (pinfunction "3_3") (pintype "passive"))
    )
    (net (code "63") (name "SPI2_SCK") (class "Default")
      (node (ref "IC7") (pin "29") (pinfunction "PB10_29") (pintype "bidirectional"))
      (node (ref "X8") (pin "5") (pinfunction "5_5") (pintype "passive"))
    )
    (net (code "64") (name "SPI3_MISO") (class "Default")
      (node (ref "IC7") (pin "52") (pinfunction "PC11_52") (pintype "bidirectional"))
      (node (ref "X7") (pin "4") (pinfunction "4_4") (pintype "passive"))
    )
    (net (code "65") (name "SPI3_MOSI") (class "Default")
      (node (ref "IC7") (pin "53") (pinfunction "PC12_53") (pintype "bidirectional"))
      (node (ref "X7") (pin "3") (pinfunction "3_3") (pintype "passive"))
    )
    (net (code "66") (name "SPI3_SCK") (class "Default")
      (node (ref "IC7") (pin "51") (pinfunction "PC10_51") (pintype "bidirectional"))
      (node (ref "X7") (pin "5") (pinfunction "5_5") (pintype "passive"))
    )
    (net (code "67") (name "SUP_DRIV") (class "Default")
      (node (ref "C61") (pin "1") (pinfunction "1_1") (pintype "passive"))
      (node (ref "C62") (pin "1") (pinfunction "1_1") (pintype "passive"))
      (node (ref "C65") (pin "1") (pinfunction "1_1") (pintype "passive"))
      (node (ref "IC1") (pin "3") (pinfunction "VIN_LDO_3") (pintype "bidirectional"))
      (node (ref "IC2") (pin "4") (pinfunction "IN_4") (pintype "bidirectional"))
      (node (ref "L4") (pin "2") (pinfunction "2_2") (pintype "passive"))
      (node (ref "R70") (pin "2") (pinfunction "2_2") (pintype "passive"))
      (node (ref "X5") (pin "17") (pinfunction "17_17") (pintype "passive"))
      (node (ref "X5") (pin "4") (pinfunction "4_4") (pintype "passive"))
    )
    (net (code "68") (name "TEMP_FET") (class "Default")
      (node (ref "R1") (pin "2") (pinfunction "2_2") (pintype "passive"))
      (node (ref "X5") (pin "13") (pinfunction "13_13") (pintype "passive"))
    )
    (net (code "69") (name "TG_U_TTL") (class "Default")
      (node (ref "IC7") (pin "37") (pinfunction "PC6_37") (pintype "bidirectional"))
      (node (ref "X5") (pin "1") (pinfunction "1_1") (pintype "passive"))
    )
    (net (code "70") (name "TG_V_TTL") (class "Default")
      (node (ref "IC7") (pin "38") (pinfunction "PC7_38") (pintype "bidirectional"))
      (node (ref "X5") (pin "2") (pinfunction "2_2") (pintype "passive"))
    )
    (net (code "71") (name "TG_W_TTL") (class "Default")
      (node (ref "IC7") (pin "39") (pinfunction "PC8_39") (pintype "bidirectional"))
      (node (ref "X5") (pin "3") (pinfunction "3_3") (pintype "passive"))
    )
    (net (code "72") (name "USART1_RX") (class "Default")
      (node (ref "IC7") (pin "43") (pinfunction "PA10_43") (pintype "bidirectional"))
      (node (ref "X6") (pin "7") (pinfunction "7_7") (pintype "passive"))
    )
    (net (code "73") (name "USART1_TX") (class "Default")
      (node (ref "IC7") (pin "42") (pinfunction "PA9_42") (pintype "bidirectional"))
      (node (ref "X6") (pin "8") (pinfunction "8_8") (pintype "passive"))
    )
    (net (code "74") (name "USER_BTN") (class "Default")
      (node (ref "C7") (pin "1") (pinfunction "1_1") (pintype "passive"))
      (node (ref "IC7") (pin "24") (pinfunction "PC4_24") (pintype "bidirectional"))
      (node (ref "R7") (pin "1") (pinfunction "1_1") (pintype "passive"))
      (node (ref "S1") (pin "P$2") (pinfunction "S_P$2") (pintype "passive"))
    )
    (net (code "75") (name "U_BAT") (class "Default")
      (node (ref "R42") (pin "1") (pinfunction "1_1") (pintype "passive"))
      (node (ref "X5") (pin "8") (pinfunction "8_8") (pintype "passive"))
    )
    (net (code "76") (name "VBAT+") (class "Default")
      (node (ref "C22") (pin "1") (pinfunction "1_1") (pintype "passive"))
      (node (ref "L3") (pin "1") (pinfunction "1_1") (pintype "passive"))
      (node (ref "X5") (pin "16") (pinfunction "16_16") (pintype "passive"))
      (node (ref "X5") (pin "5") (pinfunction "5_5") (pintype "passive"))
    )
    (net (code "77") (name "VCAP1") (class "Default")
      (node (ref "C50") (pin "1") (pinfunction "1_1") (pintype "passive"))
      (node (ref "IC7") (pin "31") (pinfunction "VCAP_1_31") (pintype "passive"))
    )
    (net (code "78") (name "VCAP2") (class "Default")
      (node (ref "C51") (pin "1") (pinfunction "1_1") (pintype "passive"))
      (node (ref "IC7") (pin "47") (pinfunction "VCAP_2_47") (pintype "passive"))
    )
    (net (code "79") (name "VDDA") (class "Default")
      (node (ref "C52") (pin "1") (pinfunction "1_1") (pintype "passive"))
      (node (ref "C54") (pin "1") (pinfunction "1_1") (pintype "passive"))
      (node (ref "IC7") (pin "13") (pinfunction "VDDA_13") (pintype "power_in"))
      (node (ref "R52") (pin "1") (pinfunction "1_1") (pintype "passive"))
    )
    (net (code "80") (name "unconnected-(IC1-NRST-Pad6)") (class "Default")
      (node (ref "IC1") (pin "6") (pinfunction "NRST_6") (pintype "bidirectional"))
    )
    (net (code "81") (name "unconnected-(IC7-PA0_WKUP-Pad14)") (class "Default")
      (node (ref "IC7") (pin "14") (pinfunction "PA0_WKUP_14") (pintype "passive"))
    )
    (net (code "82") (name "unconnected-(IC7-PA1-Pad15)") (class "Default")
      (node (ref "IC7") (pin "15") (pinfunction "PA1_15") (pintype "bidirectional"))
    )
    (net (code "83") (name "unconnected-(IC7-PA2-Pad16)") (class "Default")
      (node (ref "IC7") (pin "16") (pinfunction "PA2_16") (pintype "bidirectional"))
    )
    (net (code "84") (name "unconnected-(IC7-PA15-Pad50)") (class "Default")
      (node (ref "IC7") (pin "50") (pinfunction "PA15_50") (pintype "bidirectional"))
    )
    (net (code "85") (name "unconnected-(IC7-PB3-Pad55)") (class "Default")
      (node (ref "IC7") (pin "55") (pinfunction "PB3_55") (pintype "bidirectional"))
    )
    (net (code "86") (name "unconnected-(IC7-PB5-Pad57)") (class "Default")
      (node (ref "IC7") (pin "57") (pinfunction "PB5_57") (pintype "bidirectional"))
    )
    (net (code "87") (name "unconnected-(IC7-PB9-Pad62)") (class "Default")
      (node (ref "IC7") (pin "62") (pinfunction "PB9_62") (pintype "bidirectional"))
    )
    (net (code "88") (name "unconnected-(IC7-PC5-Pad25)") (class "Default")
      (node (ref "IC7") (pin "25") (pinfunction "PC5_25") (pintype "bidirectional"))
    )
    (net (code "89") (name "unconnected-(IC7-PC13-Pad2)") (class "Default")
      (node (ref "IC7") (pin "2") (pinfunction "PC13_2") (pintype "bidirectional"))
    )
    (net (code "90") (name "unconnected-(IC7-PC14-Pad3)") (class "Default")
      (node (ref "IC7") (pin "3") (pinfunction "PC14_3") (pintype "bidirectional"))
    )
    (net (code "91") (name "unconnected-(IC7-PC15-Pad4)") (class "Default")
      (node (ref "IC7") (pin "4") (pinfunction "PC15_4") (pintype "bidirectional"))
    )
    (net (code "92") (name "unconnected-(X5-Pad9)") (class "Default")
      (node (ref "X5") (pin "9") (pinfunction "9_9") (pintype "passive"))
    )
    (net (code "93") (name "unconnected-(X5-Pad10)") (class "Default")
      (node (ref "X5") (pin "10") (pinfunction "10_10") (pintype "passive"))
    )
    (net (code "94") (name "unconnected-(X6-Pad6)") (class "Default")
      (node (ref "X6") (pin "6") (pinfunction "6_6") (pintype "passive"))
    )
  )
)
